# floppyconv.net
KiCad netlist of a schematic drawn in EAGLE
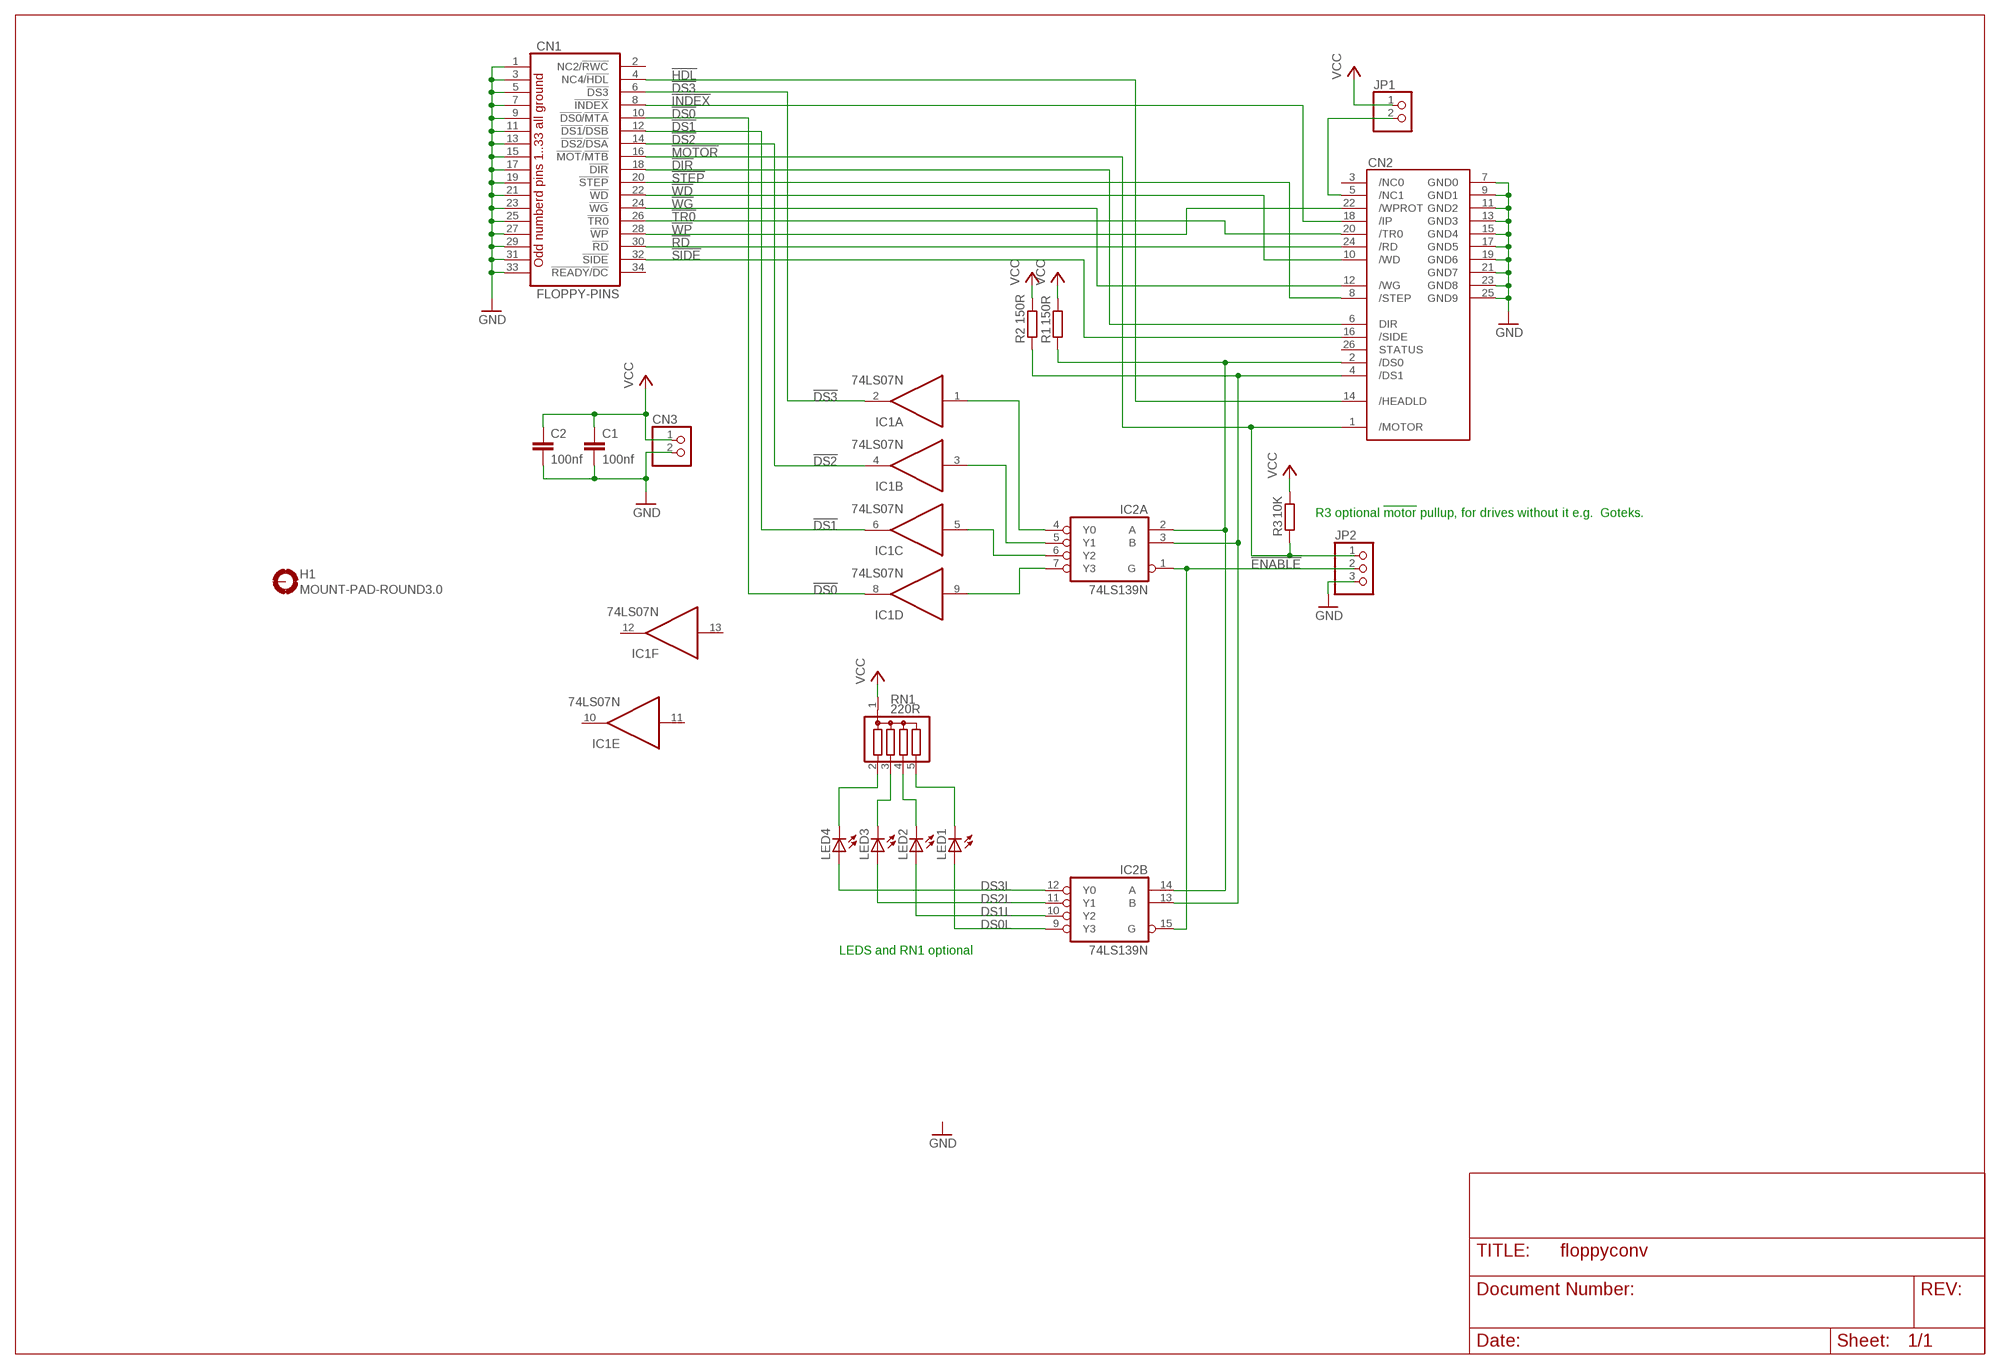
[diagram p0: schematic, sheet 1]

(export (version "E")
  (design (tool "Eeschema 10.0.6"))
  (components
    (comp (ref "C1")
      (value "100nf")
      (footprint "eagle-import:C025-025X050")
      (libsource (lib "eagle-import") (part "C-EU025-025X050"))
    )
    (comp (ref "C2")
      (value "100nf")
      (footprint "eagle-import:C025-025X050")
      (libsource (lib "eagle-import") (part "C-EU025-025X050"))
    )
    (comp (ref "CN1")
      (value "FLOPPY-PINS")
      (footprint "eagle-import:FLOPPY-PINS")
      (libsource (lib "eagle-import") (part "FLOPPY-PINS"))
    )
    (comp (ref "CN2")
      (value "DRAGON-BETA-FLOPPY")
      (footprint "eagle-import:2X13")
      (libsource (lib "eagle-import") (part "DRAGON-BETA-FLOPPY"))
    )
    (comp (ref "CN3")
      (value "PINHD-1X2")
      (footprint "eagle-import:1X02")
      (libsource (lib "eagle-import") (part "PINHD-1X2"))
    )
    (comp (ref "H1")
      (value "MOUNT-PAD-ROUND3.0")
      (footprint "eagle-import:3,0-PAD")
      (libsource (lib "eagle-import") (part "MOUNT-PAD-ROUND3.0"))
    )
    (comp (ref "IC1")
      (value "74LS07N")
      (footprint "eagle-import:DIL14")
      (libsource (lib "eagle-import") (part "7407NLS"))
    )
    (comp (ref "IC2")
      (value "74LS139N")
      (footprint "eagle-import:DIL16")
      (libsource (lib "eagle-import") (part "74139NLS"))
    )
    (comp (ref "JP1")
      (value "PINHD-1X2")
      (footprint "eagle-import:1X02")
      (libsource (lib "eagle-import") (part "PINHD-1X2"))
    )
    (comp (ref "JP2")
      (value "PINHD-1X3")
      (footprint "eagle-import:1X03")
      (libsource (lib "eagle-import") (part "PINHD-1X3"))
    )
    (comp (ref "LED1")
      (value "LED3MM")
      (footprint "eagle-import:LED3MM")
      (libsource (lib "eagle-import") (part "LED3MM"))
    )
    (comp (ref "LED2")
      (value "LED3MM")
      (footprint "eagle-import:LED3MM")
      (libsource (lib "eagle-import") (part "LED3MM"))
    )
    (comp (ref "LED3")
      (value "LED3MM")
      (footprint "eagle-import:LED3MM")
      (libsource (lib "eagle-import") (part "LED3MM"))
    )
    (comp (ref "LED4")
      (value "LED3MM")
      (footprint "eagle-import:LED3MM")
      (libsource (lib "eagle-import") (part "LED3MM"))
    )
    (comp (ref "R1")
      (value "150R")
      (footprint "eagle-import:0207_10")
      (libsource (lib "eagle-import") (part "R-EU_0207/10"))
    )
    (comp (ref "R2")
      (value "150R")
      (footprint "eagle-import:0207_10")
      (libsource (lib "eagle-import") (part "R-EU_0207/10"))
    )
    (comp (ref "R3")
      (value "10K")
      (footprint "eagle-import:0207_10")
      (libsource (lib "eagle-import") (part "R-EU_0207/10"))
    )
    (comp (ref "RN1")
      (value "220R")
      (footprint "eagle-import:SIL5R")
      (libsource (lib "eagle-import") (part "G04R-R"))
    )
  )
  (nets
    (net (code "1") (name "/DS0L") (class "Default")
      (node (ref "IC2") (pin "9") (pinfunction "Y3_9") (pintype "output"))
      (node (ref "LED1") (pin "A") (pinfunction "A_A") (pintype "passive"))
    )
    (net (code "2") (name "/DS1L") (class "Default")
      (node (ref "IC2") (pin "10") (pinfunction "Y2_10") (pintype "output"))
      (node (ref "LED2") (pin "A") (pinfunction "A_A") (pintype "passive"))
    )
    (net (code "3") (name "/DS2L") (class "Default")
      (node (ref "IC2") (pin "11") (pinfunction "Y1_11") (pintype "output"))
      (node (ref "LED3") (pin "A") (pinfunction "A_A") (pintype "passive"))
    )
    (net (code "4") (name "/DS3L") (class "Default")
      (node (ref "IC2") (pin "12") (pinfunction "Y0_12") (pintype "output"))
      (node (ref "LED4") (pin "A") (pinfunction "A_A") (pintype "passive"))
    )
    (net (code "5") (name "/~{DIR}") (class "Default")
      (node (ref "CN1") (pin "18") (pinfunction "~{DIR}_18") (pintype "open_collector"))
      (node (ref "CN2") (pin "6") (pinfunction "DIR_6") (pintype "bidirectional"))
    )
    (net (code "6") (name "/~{DS0}") (class "Default")
      (node (ref "CN1") (pin "10") (pinfunction "~{DS0}/~{MTA}_10") (pintype "open_collector"))
      (node (ref "IC1") (pin "8") (pinfunction "O_8") (pintype "open_collector"))
    )
    (net (code "7") (name "/~{DS1}") (class "Default")
      (node (ref "CN1") (pin "12") (pinfunction "~{DS1}/~{DSB}_12") (pintype "open_collector"))
      (node (ref "IC1") (pin "6") (pinfunction "O_6") (pintype "open_collector"))
    )
    (net (code "8") (name "/~{DS2}") (class "Default")
      (node (ref "CN1") (pin "14") (pinfunction "~{DS2}/~{DSA}_14") (pintype "open_collector"))
      (node (ref "IC1") (pin "4") (pinfunction "O_4") (pintype "open_collector"))
    )
    (net (code "9") (name "/~{DS3}") (class "Default")
      (node (ref "CN1") (pin "6") (pinfunction "~{DS3}_6") (pintype "open_collector"))
      (node (ref "IC1") (pin "2") (pinfunction "O_2") (pintype "open_collector"))
    )
    (net (code "10") (name "/~{ENABLE}") (class "Default")
      (node (ref "IC2") (pin "1") (pinfunction "G_1") (pintype "input"))
      (node (ref "IC2") (pin "15") (pinfunction "G_15") (pintype "input"))
      (node (ref "JP2") (pin "2") (pinfunction "2_2") (pintype "passive"))
    )
    (net (code "11") (name "/~{HDL}") (class "Default")
      (node (ref "CN1") (pin "4") (pinfunction "NC4/~{HDL}_4") (pintype "open_collector"))
      (node (ref "CN2") (pin "14") (pinfunction "/HEADLD_14") (pintype "bidirectional"))
    )
    (net (code "12") (name "/~{INDEX}") (class "Default")
      (node (ref "CN1") (pin "8") (pinfunction "~{INDEX}_8") (pintype "open_collector"))
      (node (ref "CN2") (pin "18") (pinfunction "/IP_18") (pintype "bidirectional"))
    )
    (net (code "13") (name "/~{MOTOR}") (class "Default")
      (node (ref "CN1") (pin "16") (pinfunction "~{MOT}/~{MTB}_16") (pintype "open_collector"))
      (node (ref "CN2") (pin "1") (pinfunction "/MOTOR_1") (pintype "bidirectional"))
      (node (ref "JP2") (pin "1") (pinfunction "1_1") (pintype "passive"))
      (node (ref "R3") (pin "1") (pinfunction "1_1") (pintype "passive"))
    )
    (net (code "14") (name "/~{RD}") (class "Default")
      (node (ref "CN1") (pin "30") (pinfunction "~{RD}_30") (pintype "open_collector"))
      (node (ref "CN2") (pin "24") (pinfunction "/RD_24") (pintype "bidirectional"))
    )
    (net (code "15") (name "/~{SIDE}") (class "Default")
      (node (ref "CN1") (pin "32") (pinfunction "~{SIDE}_32") (pintype "open_collector"))
      (node (ref "CN2") (pin "16") (pinfunction "/SIDE_16") (pintype "bidirectional"))
    )
    (net (code "16") (name "/~{STEP}") (class "Default")
      (node (ref "CN1") (pin "20") (pinfunction "~{STEP}_20") (pintype "open_collector"))
      (node (ref "CN2") (pin "8") (pinfunction "/STEP_8") (pintype "bidirectional"))
    )
    (net (code "17") (name "/~{TR0}") (class "Default")
      (node (ref "CN1") (pin "26") (pinfunction "~{TR0}_26") (pintype "open_collector"))
      (node (ref "CN2") (pin "20") (pinfunction "/TR0_20") (pintype "bidirectional"))
    )
    (net (code "18") (name "/~{WD}") (class "Default")
      (node (ref "CN1") (pin "22") (pinfunction "~{WD}_22") (pintype "open_collector"))
      (node (ref "CN2") (pin "10") (pinfunction "/WD_10") (pintype "bidirectional"))
    )
    (net (code "19") (name "/~{WG}") (class "Default")
      (node (ref "CN1") (pin "24") (pinfunction "~{WG}_24") (pintype "open_collector"))
      (node (ref "CN2") (pin "12") (pinfunction "/WG_12") (pintype "bidirectional"))
    )
    (net (code "20") (name "/~{WP}") (class "Default")
      (node (ref "CN1") (pin "28") (pinfunction "~{WP}_28") (pintype "open_collector"))
      (node (ref "CN2") (pin "22") (pinfunction "/WPROT_22") (pintype "bidirectional"))
    )
    (net (code "21") (name "GND") (class "Default")
      (node (ref "C1") (pin "2") (pinfunction "2_2") (pintype "passive"))
      (node (ref "C2") (pin "2") (pinfunction "2_2") (pintype "passive"))
      (node (ref "CN1") (pin "1") (pinfunction "GND_1") (pintype "power_in"))
      (node (ref "CN1") (pin "11") (pinfunction "GND_11") (pintype "power_in"))
      (node (ref "CN1") (pin "13") (pinfunction "GND_13") (pintype "power_in"))
      (node (ref "CN1") (pin "15") (pinfunction "GND_15") (pintype "power_in"))
      (node (ref "CN1") (pin "17") (pinfunction "GND_17") (pintype "power_in"))
      (node (ref "CN1") (pin "19") (pinfunction "GND_19") (pintype "power_in"))
      (node (ref "CN1") (pin "21") (pinfunction "GND_21") (pintype "power_in"))
      (node (ref "CN1") (pin "23") (pinfunction "GND_23") (pintype "power_in"))
      (node (ref "CN1") (pin "25") (pinfunction "GND_25") (pintype "power_in"))
      (node (ref "CN1") (pin "27") (pinfunction "GND_27") (pintype "power_in"))
      (node (ref "CN1") (pin "29") (pinfunction "GND_29") (pintype "power_in"))
      (node (ref "CN1") (pin "3") (pinfunction "GND_3") (pintype "power_in"))
      (node (ref "CN1") (pin "31") (pinfunction "GND_31") (pintype "power_in"))
      (node (ref "CN1") (pin "33") (pinfunction "GND_33") (pintype "power_in"))
      (node (ref "CN1") (pin "5") (pinfunction "GND_5") (pintype "power_in"))
      (node (ref "CN1") (pin "7") (pinfunction "GND_7") (pintype "power_in"))
      (node (ref "CN1") (pin "9") (pinfunction "GND_9") (pintype "power_in"))
      (node (ref "CN2") (pin "11") (pinfunction "GND2_11") (pintype "bidirectional"))
      (node (ref "CN2") (pin "13") (pinfunction "GND3_13") (pintype "bidirectional"))
      (node (ref "CN2") (pin "15") (pinfunction "GND4_15") (pintype "bidirectional"))
      (node (ref "CN2") (pin "17") (pinfunction "GND5_17") (pintype "bidirectional"))
      (node (ref "CN2") (pin "19") (pinfunction "GND6_19") (pintype "bidirectional"))
      (node (ref "CN2") (pin "21") (pinfunction "GND7_21") (pintype "bidirectional"))
      (node (ref "CN2") (pin "23") (pinfunction "GND8_23") (pintype "bidirectional"))
      (node (ref "CN2") (pin "25") (pinfunction "GND9_25") (pintype "bidirectional"))
      (node (ref "CN2") (pin "7") (pinfunction "GND0_7") (pintype "bidirectional"))
      (node (ref "CN2") (pin "9") (pinfunction "GND1_9") (pintype "bidirectional"))
      (node (ref "CN3") (pin "2") (pinfunction "2_2") (pintype "passive"))
      (node (ref "JP2") (pin "3") (pinfunction "3_3") (pintype "passive"))
    )
    (net (code "22") (name "Net-(CN2-{slash}DS0)") (class "Default")
      (node (ref "CN2") (pin "2") (pinfunction "/DS0_2") (pintype "bidirectional"))
      (node (ref "IC2") (pin "14") (pinfunction "A_14") (pintype "input"))
      (node (ref "IC2") (pin "2") (pinfunction "A_2") (pintype "input"))
      (node (ref "R1") (pin "1") (pinfunction "1_1") (pintype "passive"))
    )
    (net (code "23") (name "Net-(CN2-{slash}DS1)") (class "Default")
      (node (ref "CN2") (pin "4") (pinfunction "/DS1_4") (pintype "bidirectional"))
      (node (ref "IC2") (pin "13") (pinfunction "B_13") (pintype "input"))
      (node (ref "IC2") (pin "3") (pinfunction "B_3") (pintype "input"))
      (node (ref "R2") (pin "1") (pinfunction "1_1") (pintype "passive"))
    )
    (net (code "24") (name "Net-(CN2-{slash}NC1)") (class "Default")
      (node (ref "CN2") (pin "5") (pinfunction "/NC1_5") (pintype "bidirectional"))
      (node (ref "JP1") (pin "2") (pinfunction "2_2") (pintype "passive"))
    )
    (net (code "25") (name "Net-(IC1A-I)") (class "Default")
      (node (ref "IC1") (pin "1") (pinfunction "I_1") (pintype "input"))
      (node (ref "IC2") (pin "4") (pinfunction "Y0_4") (pintype "output"))
    )
    (net (code "26") (name "Net-(IC1B-I)") (class "Default")
      (node (ref "IC1") (pin "3") (pinfunction "I_3") (pintype "input"))
      (node (ref "IC2") (pin "5") (pinfunction "Y1_5") (pintype "output"))
    )
    (net (code "27") (name "Net-(IC1C-I)") (class "Default")
      (node (ref "IC1") (pin "5") (pinfunction "I_5") (pintype "input"))
      (node (ref "IC2") (pin "6") (pinfunction "Y2_6") (pintype "output"))
    )
    (net (code "28") (name "Net-(IC1D-I)") (class "Default")
      (node (ref "IC1") (pin "9") (pinfunction "I_9") (pintype "input"))
      (node (ref "IC2") (pin "7") (pinfunction "Y3_7") (pintype "output"))
    )
    (net (code "29") (name "Net-(LED1-C)") (class "Default")
      (node (ref "LED1") (pin "K") (pinfunction "C_K") (pintype "passive"))
      (node (ref "RN1") (pin "5") (pinfunction "5_5") (pintype "passive"))
    )
    (net (code "30") (name "Net-(LED2-C)") (class "Default")
      (node (ref "LED2") (pin "K") (pinfunction "C_K") (pintype "passive"))
      (node (ref "RN1") (pin "4") (pinfunction "4_4") (pintype "passive"))
    )
    (net (code "31") (name "Net-(LED3-C)") (class "Default")
      (node (ref "LED3") (pin "K") (pinfunction "C_K") (pintype "passive"))
      (node (ref "RN1") (pin "3") (pinfunction "3_3") (pintype "passive"))
    )
    (net (code "32") (name "Net-(LED4-C)") (class "Default")
      (node (ref "LED4") (pin "K") (pinfunction "C_K") (pintype "passive"))
      (node (ref "RN1") (pin "2") (pinfunction "2_2") (pintype "passive"))
    )
    (net (code "33") (name "VCC") (class "Default")
      (node (ref "C1") (pin "1") (pinfunction "1_1") (pintype "passive"))
      (node (ref "C2") (pin "1") (pinfunction "1_1") (pintype "passive"))
      (node (ref "CN3") (pin "1") (pinfunction "1_1") (pintype "passive"))
      (node (ref "JP1") (pin "1") (pinfunction "1_1") (pintype "passive"))
      (node (ref "R1") (pin "2") (pinfunction "2_2") (pintype "passive"))
      (node (ref "R2") (pin "2") (pinfunction "2_2") (pintype "passive"))
      (node (ref "R3") (pin "2") (pinfunction "2_2") (pintype "passive"))
      (node (ref "RN1") (pin "1") (pinfunction "1_1") (pintype "passive"))
    )
    (net (code "34") (name "unconnected-(CN1-NC2{slash}~{RWC}-Pad2)") (class "Default")
      (node (ref "CN1") (pin "2") (pinfunction "NC2/~{RWC}_2") (pintype "open_collector"))
    )
    (net (code "35") (name "unconnected-(CN1-~{READY}{slash}~{DC}-Pad34)") (class "Default")
      (node (ref "CN1") (pin "34") (pinfunction "~{READY}/~{DC}_34") (pintype "open_collector"))
    )
    (net (code "36") (name "unconnected-(CN2-STATUS-Pad26)") (class "Default")
      (node (ref "CN2") (pin "26") (pinfunction "STATUS_26") (pintype "bidirectional"))
    )
    (net (code "37") (name "unconnected-(CN2-{slash}NC0-Pad3)") (class "Default")
      (node (ref "CN2") (pin "3") (pinfunction "/NC0_3") (pintype "bidirectional"))
    )
    (net (code "38") (name "unconnected-(H1-MOUNT-PadB3,0)") (class "Default")
      (node (ref "H1") (pin "B3,0") (pinfunction "MOUNT_B3,0") (pintype "passive"))
    )
    (net (code "39") (name "unconnected-(IC1E-I-Pad11)") (class "Default")
      (node (ref "IC1") (pin "11") (pinfunction "I_11") (pintype "input"))
    )
    (net (code "40") (name "unconnected-(IC1E-O-Pad10)") (class "Default")
      (node (ref "IC1") (pin "10") (pinfunction "O_10") (pintype "open_collector"))
    )
    (net (code "41") (name "unconnected-(IC1F-I-Pad13)") (class "Default")
      (node (ref "IC1") (pin "13") (pinfunction "I_13") (pintype "input"))
    )
    (net (code "42") (name "unconnected-(IC1F-O-Pad12)") (class "Default")
      (node (ref "IC1") (pin "12") (pinfunction "O_12") (pintype "open_collector"))
    )
  )
)
